# power-v29.net
KiCad netlist of a schematic drawn in Altium Designer
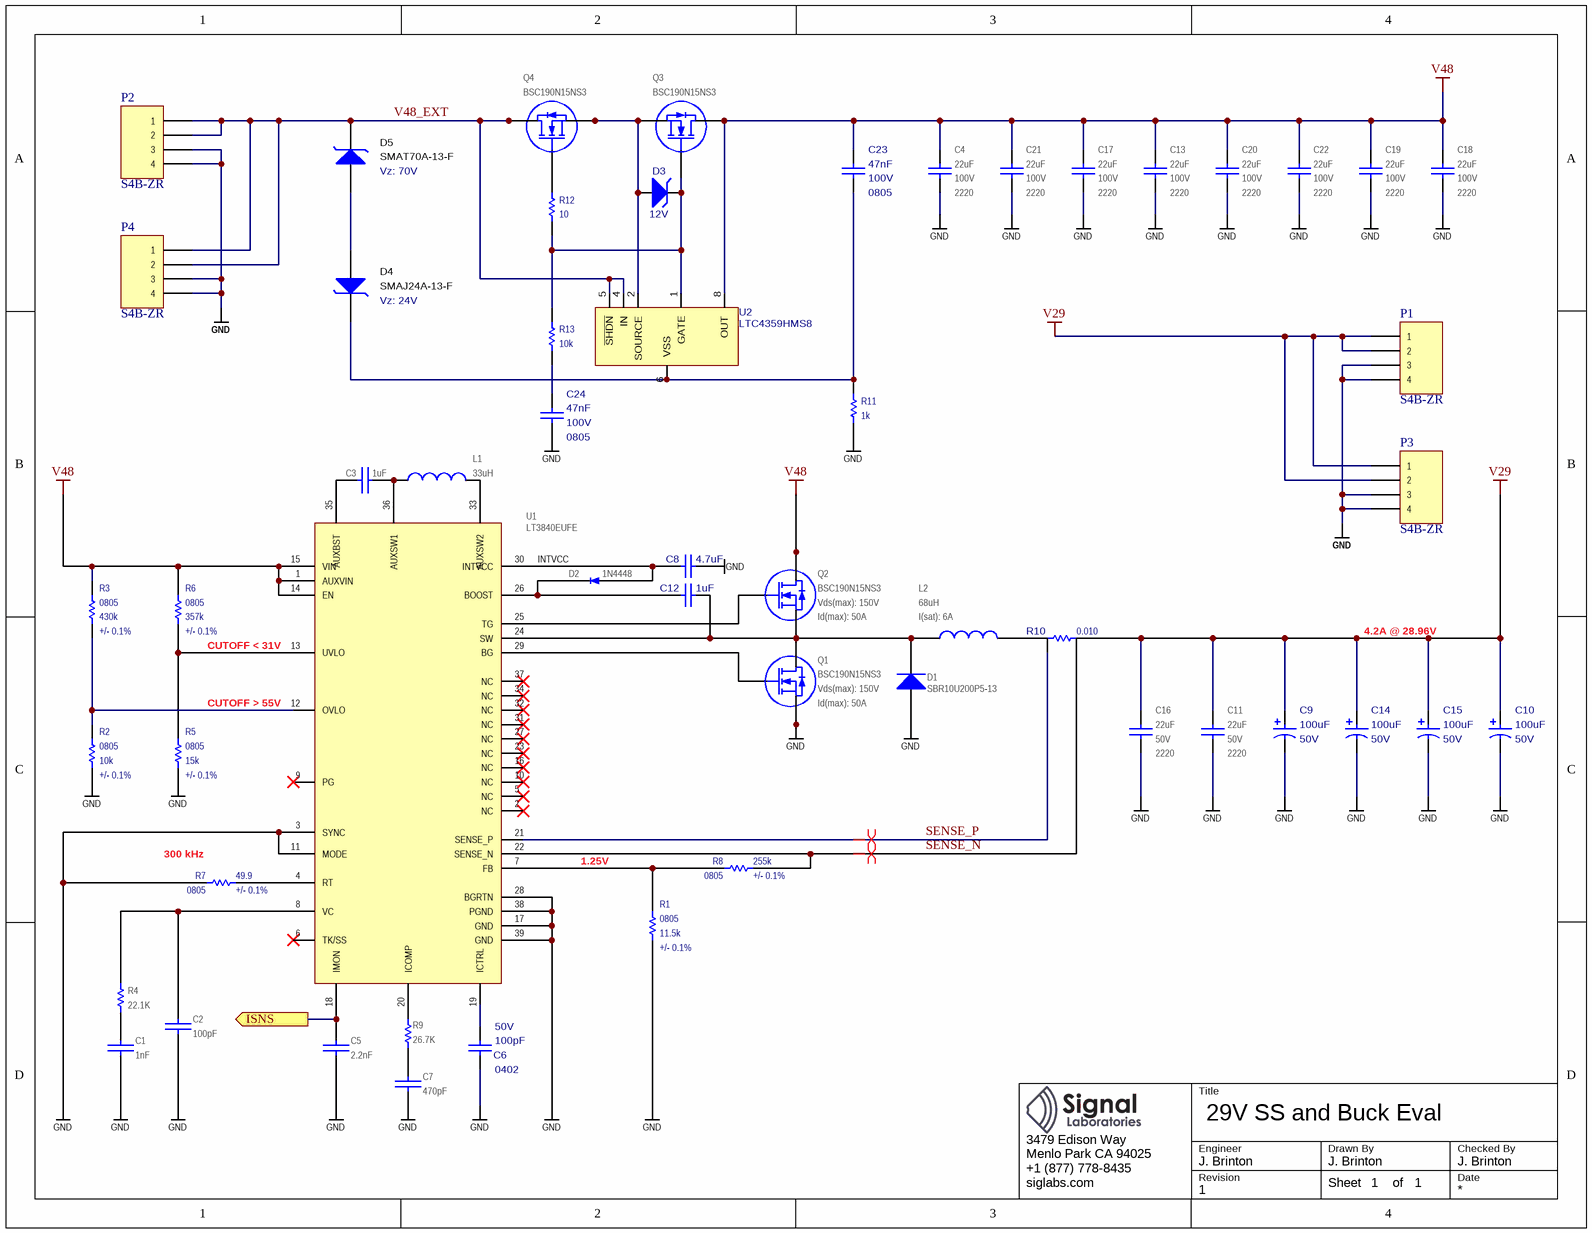
[diagram p0: power-v29.SchDoc]

(export (version "E")
  (design (tool "Eeschema 10.0.6"))
  (components
    (comp (ref "C1")
      (value "1nF")
      (footprint "CAPC100X50X55L25N")
      (description "Ceramic Capacitor 1nF ±5% 50V NP0 0402")
      (fields (field (name "MANUFACTURER") "Murata") (field (name "VOLTAGE") "50V"))
      (libsource (lib "*") (part "CAP"))
    )
    (comp (ref "C2")
      (value "100pF")
      (footprint "CAPC100X50X55L25N")
      (description "Ceramic Capacitor 100pF ±5% 50V NP0 0402")
      (fields (field (name "MANUFACTURER") "Murata") (field (name "VOLTAGE") "50V"))
      (libsource (lib "*") (part "CAP"))
    )
    (comp (ref "C3")
      (value "1uF")
      (footprint "CAPC100X50X55L25N")
      (description "Ceramic Capacitor 1uF ±10% 10V X5R 0402")
      (fields (field (name "MANUFACTURER") "Murata") (field (name "TOLERANCE") "±10%"))
      (libsource (lib "*") (part "CAP"))
    )
    (comp (ref "C4")
      (value "22uF")
      (footprint "CAPC600X500X500L160N")
      (description "Ceramic Capacitor 22uF ±20% 100V X7S Stacked")
      (fields
        (field (name "MANUFACTURER") "TDK")
        (field (name "TOLERANCE") "±20%")
        (field (name "VOLTAGE") "100V")
        (field (name "PACKAGE") "2220")
      )
      (libsource (lib "generic") (part "CAP"))
    )
    (comp (ref "C5")
      (value "2.2nF")
      (footprint "CAPC100X50X55L25N")
      (description "Ceramic Capacitor 2.2nF ±5% 25V NP0 0402")
      (fields (field (name "MANUFACTURER") "Kemet") (field (name "TOLERANCE") "±5%"))
      (libsource (lib "*") (part "CAP"))
    )
    (comp (ref "C6")
      (value "100pF")
      (footprint "CAPC160X80X90L20N")
      (description "Ceramic Capacitor 100pF ±10% 50V C0G 0402")
      (fields
        (field (name "MANUFACTURER") "Vishay")
        (field (name "TOLERANCE") "±10%")
        (field (name "PACKAGE") "0402")
        (field (name "VOLTAGE") "50V")
      )
      (libsource (lib "capacitors") (part "CAP"))
    )
    (comp (ref "C7")
      (value "470pF")
      (footprint "CAPC100X50X55L25N")
      (description "Ceramic Capacitor 470pF ±5% 50V X7R 0402")
      (fields (field (name "MANUFACTURER") "Murata") (field (name "VOLTAGE") "50V"))
      (libsource (lib "*") (part "CAP"))
    )
    (comp (ref "C8")
      (value "4.7uF")
      (footprint "CAPC160X80X90L20N")
      (description "Ceramic Capacitor 4.7uF ±10% 25V X7R 0805")
      (fields (field (name "MANUFACTURER") "Taiyo Yuden") (field (name "TOLERANCE") "±10%"))
      (libsource (lib "capacitors") (part "CAP"))
    )
    (comp (ref "C9")
      (value "100uF")
      (footprint "panasonic-ecg:CAPAE660X800D700L260X65N")
      (description "Aluminum Electrolytic Capacitor 100uF ±20% 50V")
      (fields
        (field (name "MANUFACTURER") "Panasonic")
        (field (name "TOLERANCE") "±20%")
        (field (name "VOLTAGE") "50V")
      )
      (libsource (lib "avx") (part "CAP_POL"))
    )
    (comp (ref "C10")
      (value "100uF")
      (footprint "panasonic-ecg:CAPAE660X800D700L260X65N")
      (description "Aluminum Electrolytic Capacitor 100uF ±20% 50V")
      (fields
        (field (name "MANUFACTURER") "Panasonic")
        (field (name "TOLERANCE") "±20%")
        (field (name "VOLTAGE") "50V")
      )
      (libsource (lib "avx") (part "CAP_POL"))
    )
    (comp (ref "C11")
      (value "22uF")
      (footprint "CAPC600X500X500L160N")
      (description "Ceramic Capacitor 22uF ±20% 50V X7S Stacked")
      (fields
        (field (name "MANUFACTURER") "TDK")
        (field (name "TOLERANCE") "±20%")
        (field (name "VOLTAGE") "50V")
        (field (name "PACKAGE") "2220")
      )
      (libsource (lib "generic") (part "CAP"))
    )
    (comp (ref "C12")
      (value "1uF")
      (footprint "CAPC160X80X90L20N")
      (description "Ceramic Capacitor 1uF ±10% 50V X7R 0805")
      (fields (field (name "MANUFACTURER") "Taiyo Yuden") (field (name "TOLERANCE") "±10%"))
      (libsource (lib "capacitors") (part "CAP"))
    )
    (comp (ref "C13")
      (value "22uF")
      (footprint "CAPC600X500X500L160N")
      (description "Ceramic Capacitor 22uF ±20% 100V X7S Stacked")
      (fields
        (field (name "MANUFACTURER") "TDK")
        (field (name "TOLERANCE") "±20%")
        (field (name "VOLTAGE") "100V")
        (field (name "PACKAGE") "2220")
      )
      (libsource (lib "generic") (part "CAP"))
    )
    (comp (ref "C14")
      (value "100uF")
      (footprint "panasonic-ecg:CAPAE660X800D700L260X65N")
      (description "Aluminum Electrolytic Capacitor 100uF ±20% 50V")
      (fields
        (field (name "MANUFACTURER") "Panasonic")
        (field (name "TOLERANCE") "±20%")
        (field (name "VOLTAGE") "50V")
      )
      (libsource (lib "avx") (part "CAP_POL"))
    )
    (comp (ref "C15")
      (value "100uF")
      (footprint "panasonic-ecg:CAPAE660X800D700L260X65N")
      (description "Aluminum Electrolytic Capacitor 100uF ±20% 50V")
      (fields
        (field (name "MANUFACTURER") "Panasonic")
        (field (name "TOLERANCE") "±20%")
        (field (name "VOLTAGE") "50V")
      )
      (libsource (lib "avx") (part "CAP_POL"))
    )
    (comp (ref "C16")
      (value "22uF")
      (footprint "CAPC600X500X500L160N")
      (description "Ceramic Capacitor 22uF ±20% 50V X7S Stacked")
      (fields
        (field (name "MANUFACTURER") "TDK")
        (field (name "TOLERANCE") "±20%")
        (field (name "VOLTAGE") "50V")
        (field (name "PACKAGE") "2220")
      )
      (libsource (lib "generic") (part "CAP"))
    )
    (comp (ref "C17")
      (value "22uF")
      (footprint "CAPC600X500X500L160N")
      (description "Ceramic Capacitor 22uF ±20% 100V X7S Stacked")
      (fields
        (field (name "MANUFACTURER") "TDK")
        (field (name "TOLERANCE") "±20%")
        (field (name "VOLTAGE") "100V")
        (field (name "PACKAGE") "2220")
      )
      (libsource (lib "generic") (part "CAP"))
    )
    (comp (ref "C18")
      (value "22uF")
      (footprint "CAPC600X500X500L160N")
      (description "Ceramic Capacitor 22uF ±20% 100V X7S Stacked")
      (fields
        (field (name "MANUFACTURER") "TDK")
        (field (name "TOLERANCE") "±20%")
        (field (name "VOLTAGE") "100V")
        (field (name "PACKAGE") "2220")
      )
      (libsource (lib "generic") (part "CAP"))
    )
    (comp (ref "C19")
      (value "22uF")
      (footprint "CAPC600X500X500L160N")
      (description "Ceramic Capacitor 22uF ±20% 100V X7S Stacked")
      (fields
        (field (name "MANUFACTURER") "TDK")
        (field (name "TOLERANCE") "±20%")
        (field (name "VOLTAGE") "100V")
        (field (name "PACKAGE") "2220")
      )
      (libsource (lib "generic") (part "CAP"))
    )
    (comp (ref "C20")
      (value "22uF")
      (footprint "CAPC600X500X500L160N")
      (description "Ceramic Capacitor 22uF ±20% 100V X7S Stacked")
      (fields
        (field (name "MANUFACTURER") "TDK")
        (field (name "TOLERANCE") "±20%")
        (field (name "VOLTAGE") "100V")
        (field (name "PACKAGE") "2220")
      )
      (libsource (lib "generic") (part "CAP"))
    )
    (comp (ref "C21")
      (value "22uF")
      (footprint "CAPC600X500X500L160N")
      (description "Ceramic Capacitor 22uF ±20% 100V X7S Stacked")
      (fields
        (field (name "MANUFACTURER") "TDK")
        (field (name "TOLERANCE") "±20%")
        (field (name "VOLTAGE") "100V")
        (field (name "PACKAGE") "2220")
      )
      (libsource (lib "generic") (part "CAP"))
    )
    (comp (ref "C22")
      (value "22uF")
      (footprint "CAPC600X500X500L160N")
      (description "Ceramic Capacitor 22uF ±20% 100V X7S Stacked")
      (fields
        (field (name "MANUFACTURER") "TDK")
        (field (name "TOLERANCE") "±20%")
        (field (name "VOLTAGE") "100V")
        (field (name "PACKAGE") "2220")
      )
      (libsource (lib "generic") (part "CAP"))
    )
    (comp (ref "C23")
      (value "47nF")
      (footprint "CAPC200X125X145L45N")
      (description "Ceramic Capacitor 47nF ±10% 100V X7R 0805")
      (fields
        (field (name "MANUFACTURER") "Vishay")
        (field (name "TOLERANCE") "±10%")
        (field (name "PACKAGE") "0805")
        (field (name "VOLTAGE") "100V")
      )
      (libsource (lib "capacitors") (part "CAP"))
    )
    (comp (ref "C24")
      (value "47nF")
      (footprint "CAPC200X125X145L45N")
      (description "Ceramic Capacitor 47nF ±10% 100V X7R 0805")
      (fields
        (field (name "MANUFACTURER") "Vishay")
        (field (name "TOLERANCE") "±10%")
        (field (name "PACKAGE") "0805")
        (field (name "VOLTAGE") "100V")
      )
      (libsource (lib "capacitors") (part "CAP"))
    )
    (comp (ref "D1")
      (value "SBR10U200P5-13")
      (footprint "DIODES_POWERDI5")
      (description "Schottky Diode 200V 10A SMD")
      (fields (field (name "MANUFACTURER") "Diodes Inc"))
      (libsource (lib "diodes_inc") (part "PDS5100H"))
    )
    (comp (ref "D2")
      (value "1N4448HWS-7-F")
      (footprint "diodes_inc:SOD323")
      (description "Schottky Diode 80V 250mA SOD323")
      (fields (field (name "MANUFACTURER") "Diodes, Inc.") (field (name "ALTERNATIVE P/N") "1N4448"))
      (libsource (lib "diodes_inc") (part "1N4448HWS-7-F"))
    )
    (comp (ref "D3")
      (value "DDZ12BQ-7")
      (footprint "SOD123")
      (description "Zener Diode 12V 370mW SOD-123")
      (fields (field (name "MANUFACTURER") "Diodes, Inc.") (field (name "VZ") "12V"))
      (libsource (lib "generic") (part "ZENER"))
    )
    (comp (ref "D4")
      (value "SMAJ24A-13-F")
      (footprint "SMA")
      (description "TVS Diode 24V/38.9V SMA")
      (fields (field (name "MANUFACTURER") "Diodes, Inc.") (field (name "VZ") "24V"))
      (libsource (lib "generic") (part "TVS"))
    )
    (comp (ref "D5")
      (value "SMAT70A-13-F")
      (footprint "SMA")
      (description "TVS Diode 70V/100V SMA")
      (fields (field (name "MANUFACTURER") "Diodes, Inc.") (field (name "VZ") "70V"))
      (libsource (lib "generic") (part "TVS"))
    )
    (comp (ref "L1")
      (value "33uH")
      (footprint "coilcraft:ME3220")
      (description "Wirewound Power Inductor 33uH ±10% 500mA SMD")
      (fields (field (name "MANUFACTURER") "Coilcraft") (field (name "TOLERANCE") "±10%"))
      (libsource (lib "CamBoard_Pico_70.19K") (part "COIL"))
    )
    (comp (ref "L2")
      (value "68uH")
      (footprint "cooper:HCM1A1707")
      (description "Fixed Inductor 68uH, 6A(sat), SMD")
      (fields
        (field (name "MANUFACTURER") "Eaton")
        (field (name "I(SAT)") "6A")
        (field (name "Comment") "HCM1A1707-680-R")
      )
      (libsource (lib "CamBoard_Pico_70.19K") (part "COIL"))
    )
    (comp (ref "P1")
      (value "S4B-ZR")
      (footprint "jst:S4B-ZR")
      (description "1.5mm pitch right angle 6-position")
      (fields (field (name "MANUFACTURER") "JST"))
      (libsource (lib "jst") (part "S4B-ZR"))
    )
    (comp (ref "P2")
      (value "S4B-ZR")
      (footprint "jst:S4B-ZR")
      (description "1.5mm pitch right angle 6-position")
      (fields (field (name "MANUFACTURER") "JST"))
      (libsource (lib "") (part "S4B-ZR_1"))
    )
    (comp (ref "P3")
      (value "S4B-ZR")
      (footprint "jst:S4B-ZR")
      (description "1.5mm pitch right angle 6-position")
      (fields (field (name "MANUFACTURER") "JST"))
      (libsource (lib "jst") (part "S4B-ZR"))
    )
    (comp (ref "P4")
      (value "S4B-ZR")
      (footprint "jst:S4B-ZR")
      (description "1.5mm pitch right angle 6-position")
      (fields (field (name "MANUFACTURER") "JST"))
      (libsource (lib "") (part "S4B-ZR_1"))
    )
    (comp (ref "Q1")
      (value "BSC190N15NS3")
      (footprint "TDSON-8")
      (description "MOSFET N-Channel Enhancement Mode")
      (fields
        (field (name "MANUFACTURER") "Infineon")
        (field (name "VDS(MAX)") "150V")
        (field (name "ID(MAX)") "50A")
      )
      (libsource (lib "infinion") (part "BSC190N15NS3"))
    )
    (comp (ref "Q2")
      (value "BSC190N15NS3")
      (footprint "TDSON-8")
      (description "MOSFET N-Channel Enhancement Mode")
      (fields
        (field (name "MANUFACTURER") "Infineon")
        (field (name "VDS(MAX)") "150V")
        (field (name "ID(MAX)") "50A")
      )
      (libsource (lib "infinion") (part "BSC190N15NS3"))
    )
    (comp (ref "Q3")
      (value "BSC190N15NS3")
      (footprint "TDSON-8")
      (description "MOSFET N-Channel Enhancement Mode")
      (fields (field (name "MANUFACTURER") "Infineon"))
      (libsource (lib "infinion") (part "BSC190N15NS3"))
    )
    (comp (ref "Q4")
      (value "BSC190N15NS3")
      (footprint "TDSON-8")
      (description "MOSFET N-Channel Enhancement Mode")
      (fields (field (name "MANUFACTURER") "Infineon"))
      (libsource (lib "infinion") (part "BSC190N15NS3"))
    )
    (comp (ref "R1")
      (value "11.5k")
      (footprint "RESC2012X70N")
      (description "Thin Film Resistor 11.5k +/-0.1% SMD 0805")
      (fields
        (field (name "TOLERANCE") "+/- 0.1%")
        (field (name "MANUFACTURER") "Yageo")
        (field (name "PACKAGE") "0805")
        (field (name "Comment") "RT0805BRD0711K5L")
      )
      (libsource (lib "generic") (part "RES"))
    )
    (comp (ref "R2")
      (value "10k")
      (footprint "RESC2012X70N")
      (description "Thin Film Resistor 10k +/-0.1% SMD 0805")
      (fields
        (field (name "TOLERANCE") "+/- 0.1%")
        (field (name "MANUFACTURER") "Susumu")
        (field (name "PACKAGE") "0805")
        (field (name "Comment") "RG2012P-103-B-T5")
      )
      (libsource (lib "generic") (part "RES"))
    )
    (comp (ref "R3")
      (value "430k")
      (footprint "RESC2012X70N")
      (description "Thin Film Resistor 430k +/-0.1% SMD 0805")
      (fields
        (field (name "TOLERANCE") "+/- 0.1%")
        (field (name "MANUFACTURER") "Yageo")
        (field (name "PACKAGE") "0805")
        (field (name "Comment") "RT0805BRD07430KL")
      )
      (libsource (lib "generic") (part "RES"))
    )
    (comp (ref "R4")
      (value "22.1K")
      (footprint "generic:RESC1005X40N")
      (description "Thick Film Resistor 22.1k ±1% 0402")
      (fields (field (name "MANUFACTURER") "Panasonic") (field (name "TOLERANCE") "±1%"))
      (libsource (lib "Graviton") (part "RES 0402"))
    )
    (comp (ref "R5")
      (value "15k")
      (footprint "RESC2012X70N")
      (description "Thin Film Resistor 15k +/-0.1% SMD 0805")
      (fields
        (field (name "TOLERANCE") "+/- 0.1%")
        (field (name "MANUFACTURER") "Susumu")
        (field (name "PACKAGE") "0805")
        (field (name "Comment") "RG2012P-153-B-T5")
      )
      (libsource (lib "generic") (part "RES"))
    )
    (comp (ref "R6")
      (value "357k")
      (footprint "RESC2012X70N")
      (description "Thin Film Resistor 357k +/-0.1% SMD 0805")
      (fields
        (field (name "TOLERANCE") "+/- 0.1%")
        (field (name "MANUFACTURER") "Yageo")
        (field (name "PACKAGE") "0805")
        (field (name "Comment") "RT0805BRD07357KL")
      )
      (libsource (lib "generic") (part "RES"))
    )
    (comp (ref "R7")
      (value "49.9")
      (footprint "RESC2012X70N")
      (description "Thin Film Resistor 49 +/-0.1% SMD 0805")
      (fields
        (field (name "TOLERANCE") "+/- 0.1%")
        (field (name "MANUFACTURER") "Yageo")
        (field (name "PACKAGE") "0805")
        (field (name "Comment") "RT0805BRD0749R9L")
      )
      (libsource (lib "generic") (part "RES"))
    )
    (comp (ref "R8")
      (value "255k")
      (footprint "RESC2012X70N")
      (description "Thin Film Resistor 255k +/-0.1% SMD 0805")
      (fields
        (field (name "TOLERANCE") "+/- 0.1%")
        (field (name "MANUFACTURER") "Vishay")
        (field (name "PACKAGE") "0805")
        (field (name "Comment") "PTN0805E2553BST1")
      )
      (libsource (lib "generic") (part "RES"))
    )
    (comp (ref "R9")
      (value "26.7K")
      (footprint "generic:RESC1005X40N")
      (description "Thick Film Resistor 26.7k ±1% 0402")
      (fields (field (name "MANUFACTURER") "Panasonic") (field (name "TOLERANCE") "±1%"))
      (libsource (lib "Graviton") (part "RES 0402"))
    )
    (comp (ref "R10")
      (value "0.010")
      (footprint "ohmite:LVK20")
      (description "Current Sense Resistor 10 mOhms +/-0.5% SMD 4-Terminal")
      (fields (field (name "TOLERANCE") "+/-0.5%") (field (name "MANUFACTURER") "Ohmite"))
      (libsource (lib "bourns") (part "CST0612-FC-R002E"))
    )
    (comp (ref "R11")
      (value "1k")
      (footprint "RESC2012X70N")
      (description "Thin Film Resistor 1k +/-1% SMD 0805")
      (fields (field (name "TOLERANCE") "+/- 1%") (field (name "MANUFACTURER") "Yageo"))
      (libsource (lib "generic") (part "RES"))
    )
    (comp (ref "R12")
      (value "10")
      (footprint "RESC2012X70N")
      (description "Thin Film Resistor 10 +/-1% SMD 0805")
      (fields (field (name "TOLERANCE") "+/- 1%") (field (name "MANUFACTURER") "Yageo"))
      (libsource (lib "generic") (part "RES"))
    )
    (comp (ref "R13")
      (value "10k")
      (footprint "RESC2012X70N")
      (description "Thin Film Resistor 10k +/-1% SMD 0805")
      (fields (field (name "TOLERANCE") "+/- 1%") (field (name "MANUFACTURER") "Yageo"))
      (libsource (lib "generic") (part "RES"))
    )
    (comp (ref "U1")
      (value "LT3840EUFE")
      (footprint "linear:QFN39P40_600X400X80L40X20T465X265N")
      (description "Synchronous Regulator Controller")
      (fields (field (name "MANUFACTURER") "Linear Technologies"))
      (libsource (lib "linear") (part "LT3840EUFE"))
    )
    (comp (ref "U2")
      (value "LTC4359HMS8")
      (footprint "generic:MSOP8")
      (description "Ideal Diode Controller")
      (fields (field (name "MANUFACTURER") "Linear Technology"))
      (libsource (lib "linear") (part "LTC4359HMS8"))
    )
  )
  (nets
    (net (code "1") (name "/INTVCC") (class "Default")
      (node (ref "C8") (pin "1") (pinfunction "1_1") (pintype "passive"))
      (node (ref "D2") (pin "A") (pinfunction "A_A") (pintype "passive"))
      (node (ref "U1") (pin "30") (pinfunction "INTVCC_30") (pintype "passive"))
    )
    (net (code "2") (name "/ISNS") (class "Default")
      (node (ref "C5") (pin "1") (pinfunction "1_1") (pintype "passive"))
      (node (ref "U1") (pin "18") (pinfunction "IMON_18") (pintype "passive"))
    )
    (net (code "3") (name "/SENSE_N") (class "Default")
      (node (ref "R10") (pin "2") (pinfunction "2_2") (pintype "passive"))
      (node (ref "R8") (pin "1") (pinfunction "1_1") (pintype "passive"))
      (node (ref "U1") (pin "22") (pinfunction "SENSE_N_22") (pintype "passive"))
    )
    (net (code "4") (name "/SENSE_P") (class "Default")
      (node (ref "R10") (pin "3") (pinfunction "3_3") (pintype "passive"))
      (node (ref "U1") (pin "21") (pinfunction "SENSE_P_21") (pintype "passive"))
    )
    (net (code "5") (name "/V48_EXT") (class "Default")
      (node (ref "D5") (pin "2") (pinfunction "K_2") (pintype "passive"))
      (node (ref "P2") (pin "1") (pinfunction "1_1") (pintype "passive"))
      (node (ref "P2") (pin "2") (pinfunction "2_2") (pintype "passive"))
      (node (ref "P4") (pin "1") (pinfunction "1_1") (pintype "passive"))
      (node (ref "P4") (pin "2") (pinfunction "2_2") (pintype "passive"))
      (node (ref "Q4") (pin "5") (pinfunction "D_5") (pintype "passive"))
      (node (ref "Q4") (pin "6") (pinfunction "D_6") (pintype "passive"))
      (node (ref "Q4") (pin "7") (pinfunction "D_7") (pintype "passive"))
      (node (ref "Q4") (pin "8") (pinfunction "D_8") (pintype "passive"))
      (node (ref "Q4") (pin "9") (pinfunction "D_9") (pintype "passive"))
      (node (ref "U2") (pin "4") (pinfunction "IN_4") (pintype "passive"))
      (node (ref "U2") (pin "5") (pinfunction "SHDN_5") (pintype "passive"))
    )
    (net (code "6") (name "GND") (class "Default")
      (node (ref "C1") (pin "2") (pinfunction "2_2") (pintype "passive"))
      (node (ref "C10") (pin "2") (pinfunction "2_2") (pintype "passive"))
      (node (ref "C11") (pin "1") (pinfunction "1_1") (pintype "passive"))
      (node (ref "C13") (pin "1") (pinfunction "1_1") (pintype "passive"))
      (node (ref "C14") (pin "2") (pinfunction "2_2") (pintype "passive"))
      (node (ref "C15") (pin "2") (pinfunction "2_2") (pintype "passive"))
      (node (ref "C16") (pin "1") (pinfunction "1_1") (pintype "passive"))
      (node (ref "C17") (pin "1") (pinfunction "1_1") (pintype "passive"))
      (node (ref "C18") (pin "1") (pinfunction "1_1") (pintype "passive"))
      (node (ref "C19") (pin "1") (pinfunction "1_1") (pintype "passive"))
      (node (ref "C2") (pin "1") (pinfunction "1_1") (pintype "passive"))
      (node (ref "C20") (pin "1") (pinfunction "1_1") (pintype "passive"))
      (node (ref "C21") (pin "1") (pinfunction "1_1") (pintype "passive"))
      (node (ref "C22") (pin "1") (pinfunction "1_1") (pintype "passive"))
      (node (ref "C24") (pin "2") (pinfunction "2_2") (pintype "passive"))
      (node (ref "C4") (pin "1") (pinfunction "1_1") (pintype "passive"))
      (node (ref "C5") (pin "2") (pinfunction "2_2") (pintype "passive"))
      (node (ref "C6") (pin "2") (pinfunction "2_2") (pintype "passive"))
      (node (ref "C7") (pin "1") (pinfunction "1_1") (pintype "passive"))
      (node (ref "C8") (pin "2") (pinfunction "2_2") (pintype "passive"))
      (node (ref "C9") (pin "2") (pinfunction "2_2") (pintype "passive"))
      (node (ref "D1") (pin "A") (pinfunction "A_A") (pintype "power_in"))
      (node (ref "P1") (pin "3") (pinfunction "3_3") (pintype "passive"))
      (node (ref "P1") (pin "4") (pinfunction "4_4") (pintype "passive"))
      (node (ref "P2") (pin "3") (pinfunction "3_3") (pintype "passive"))
      (node (ref "P2") (pin "4") (pinfunction "4_4") (pintype "passive"))
      (node (ref "P3") (pin "3") (pinfunction "3_3") (pintype "passive"))
      (node (ref "P3") (pin "4") (pinfunction "4_4") (pintype "passive"))
      (node (ref "P4") (pin "3") (pinfunction "3_3") (pintype "passive"))
      (node (ref "P4") (pin "4") (pinfunction "4_4") (pintype "passive"))
      (node (ref "Q1") (pin "1") (pinfunction "S_1") (pintype "passive"))
      (node (ref "Q1") (pin "2") (pinfunction "S_2") (pintype "passive"))
      (node (ref "Q1") (pin "3") (pinfunction "S_3") (pintype "passive"))
      (node (ref "R1") (pin "1") (pinfunction "1_1") (pintype "passive"))
      (node (ref "R11") (pin "1") (pinfunction "1_1") (pintype "passive"))
      (node (ref "R2") (pin "1") (pinfunction "1_1") (pintype "passive"))
      (node (ref "R5") (pin "1") (pinfunction "1_1") (pintype "passive"))
      (node (ref "R7") (pin "2") (pinfunction "2_2") (pintype "passive"))
      (node (ref "U1") (pin "11") (pinfunction "MODE_11") (pintype "passive"))
      (node (ref "U1") (pin "17") (pinfunction "GND_17") (pintype "passive"))
      (node (ref "U1") (pin "28") (pinfunction "BGRTN_28") (pintype "passive"))
      (node (ref "U1") (pin "3") (pinfunction "SYNC_3") (pintype "passive"))
      (node (ref "U1") (pin "38") (pinfunction "PGND_38") (pintype "passive"))
      (node (ref "U1") (pin "39") (pinfunction "GND_39") (pintype "passive"))
    )
    (net (code "7") (name "Net-(C1-Pad1)") (class "Default")
      (node (ref "C1") (pin "1") (pinfunction "1_1") (pintype "passive"))
      (node (ref "R4") (pin "1") (pinfunction "1_1") (pintype "passive"))
    )
    (net (code "8") (name "Net-(C7-Pad2)") (class "Default")
      (node (ref "C7") (pin "2") (pinfunction "2_2") (pintype "passive"))
      (node (ref "R9") (pin "2") (pinfunction "2_2") (pintype "passive"))
    )
    (net (code "9") (name "Net-(C24-Pad1)") (class "Default")
      (node (ref "C24") (pin "1") (pinfunction "1_1") (pintype "passive"))
      (node (ref "R13") (pin "1") (pinfunction "1_1") (pintype "passive"))
    )
    (net (code "10") (name "Net-(D3-A)") (class "Default")
      (node (ref "D3") (pin "1") (pinfunction "A_1") (pintype "power_in"))
      (node (ref "Q3") (pin "1") (pinfunction "S_1") (pintype "passive"))
      (node (ref "Q3") (pin "2") (pinfunction "S_2") (pintype "passive"))
      (node (ref "Q3") (pin "3") (pinfunction "S_3") (pintype "passive"))
      (node (ref "Q4") (pin "1") (pinfunction "S_1") (pintype "passive"))
      (node (ref "Q4") (pin "2") (pinfunction "S_2") (pintype "passive"))
      (node (ref "Q4") (pin "3") (pinfunction "S_3") (pintype "passive"))
      (node (ref "U2") (pin "2") (pinfunction "SOURCE_2") (pintype "passive"))
    )
    (net (code "11") (name "Net-(D3-K)") (class "Default")
      (node (ref "D3") (pin "2") (pinfunction "K_2") (pintype "passive"))
      (node (ref "Q3") (pin "4") (pinfunction "G_4") (pintype "passive"))
      (node (ref "R12") (pin "1") (pinfunction "1_1") (pintype "passive"))
      (node (ref "R13") (pin "2") (pinfunction "2_2") (pintype "passive"))
      (node (ref "U2") (pin "1") (pinfunction "GATE_1") (pintype "passive"))
    )
    (net (code "12") (name "Net-(D4-A)") (class "Default")
      (node (ref "D4") (pin "1") (pinfunction "A_1") (pintype "power_in"))
      (node (ref "D5") (pin "1") (pinfunction "A_1") (pintype "power_in"))
    )
    (net (code "13") (name "Net-(D4-K)") (class "Default")
      (node (ref "C23") (pin "2") (pinfunction "2_2") (pintype "passive"))
      (node (ref "D4") (pin "2") (pinfunction "K_2") (pintype "passive"))
      (node (ref "R11") (pin "2") (pinfunction "2_2") (pintype "passive"))
      (node (ref "U2") (pin "6") (pinfunction "VSS_6") (pintype "passive"))
    )
    (net (code "14") (name "Net-(L2-Pad2)") (class "Default")
      (node (ref "L2") (pin "2") (pinfunction "2_2") (pintype "passive"))
      (node (ref "R10") (pin "4") (pinfunction "4_4") (pintype "passive"))
    )
    (net (code "15") (name "Net-(Q1-G)") (class "Default")
      (node (ref "Q1") (pin "4") (pinfunction "G_4") (pintype "passive"))
      (node (ref "U1") (pin "29") (pinfunction "BG_29") (pintype "passive"))
    )
    (net (code "16") (name "Net-(Q2-G)") (class "Default")
      (node (ref "Q2") (pin "4") (pinfunction "G_4") (pintype "passive"))
      (node (ref "U1") (pin "25") (pinfunction "TG_25") (pintype "passive"))
    )
    (net (code "17") (name "Net-(Q4-G)") (class "Default")
      (node (ref "Q4") (pin "4") (pinfunction "G_4") (pintype "passive"))
      (node (ref "R12") (pin "2") (pinfunction "2_2") (pintype "passive"))
    )
    (net (code "18") (name "Net-(U1-AUXBST)") (class "Default")
      (node (ref "C3") (pin "2") (pinfunction "2_2") (pintype "passive"))
      (node (ref "U1") (pin "35") (pinfunction "AUXBST_35") (pintype "passive"))
    )
    (net (code "19") (name "Net-(U1-AUXSW1)") (class "Default")
      (node (ref "C3") (pin "1") (pinfunction "1_1") (pintype "passive"))
      (node (ref "L1") (pin "1") (pinfunction "1_1") (pintype "passive"))
      (node (ref "U1") (pin "36") (pinfunction "AUXSW1_36") (pintype "passive"))
    )
    (net (code "20") (name "Net-(U1-AUXSW2)") (class "Default")
      (node (ref "L1") (pin "2") (pinfunction "2_2") (pintype "passive"))
      (node (ref "U1") (pin "33") (pinfunction "AUXSW2_33") (pintype "passive"))
    )
    (net (code "21") (name "Net-(U1-BOOST)") (class "Default")
      (node (ref "C12") (pin "1") (pinfunction "1_1") (pintype "passive"))
      (node (ref "D2") (pin "K") (pinfunction "K_K") (pintype "passive"))
      (node (ref "U1") (pin "26") (pinfunction "BOOST_26") (pintype "passive"))
    )
    (net (code "22") (name "Net-(U1-FB)") (class "Default")
      (node (ref "R1") (pin "2") (pinfunction "2_2") (pintype "passive"))
      (node (ref "R8") (pin "2") (pinfunction "2_2") (pintype "passive"))
      (node (ref "U1") (pin "7") (pinfunction "FB_7") (pintype "passive"))
    )
    (net (code "23") (name "Net-(U1-ICOMP)") (class "Default")
      (node (ref "R9") (pin "1") (pinfunction "1_1") (pintype "passive"))
      (node (ref "U1") (pin "20") (pinfunction "ICOMP_20") (pintype "passive"))
    )
    (net (code "24") (name "Net-(U1-ICTRL)") (class "Default")
      (node (ref "C6") (pin "1") (pinfunction "1_1") (pintype "passive"))
      (node (ref "U1") (pin "19") (pinfunction "ICTRL_19") (pintype "passive"))
    )
    (net (code "25") (name "Net-(U1-OVLO)") (class "Default")
      (node (ref "R2") (pin "2") (pinfunction "2_2") (pintype "passive"))
      (node (ref "R3") (pin "1") (pinfunction "1_1") (pintype "passive"))
      (node (ref "U1") (pin "12") (pinfunction "OVLO_12") (pintype "passive"))
    )
    (net (code "26") (name "Net-(U1-RT)") (class "Default")
      (node (ref "R7") (pin "1") (pinfunction "1_1") (pintype "passive"))
      (node (ref "U1") (pin "4") (pinfunction "RT_4") (pintype "passive"))
    )
    (net (code "27") (name "Net-(U1-SW)") (class "Default")
      (node (ref "C12") (pin "2") (pinfunction "2_2") (pintype "passive"))
      (node (ref "D1") (pin "K") (pinfunction "K_K") (pintype "passive"))
      (node (ref "L2") (pin "1") (pinfunction "1_1") (pintype "passive"))
      (node (ref "Q1") (pin "5") (pinfunction "D_5") (pintype "passive"))
      (node (ref "Q1") (pin "6") (pinfunction "D_6") (pintype "passive"))
      (node (ref "Q1") (pin "7") (pinfunction "D_7") (pintype "passive"))
      (node (ref "Q1") (pin "8") (pinfunction "D_8") (pintype "passive"))
      (node (ref "Q1") (pin "9") (pinfunction "D_9") (pintype "passive"))
      (node (ref "Q2") (pin "1") (pinfunction "S_1") (pintype "passive"))
      (node (ref "Q2") (pin "2") (pinfunction "S_2") (pintype "passive"))
      (node (ref "Q2") (pin "3") (pinfunction "S_3") (pintype "passive"))
      (node (ref "U1") (pin "24") (pinfunction "SW_24") (pintype "passive"))
    )
    (net (code "28") (name "Net-(U1-UVLO)") (class "Default")
      (node (ref "R5") (pin "2") (pinfunction "2_2") (pintype "passive"))
      (node (ref "R6") (pin "1") (pinfunction "1_1") (pintype "passive"))
      (node (ref "U1") (pin "13") (pinfunction "UVLO_13") (pintype "passive"))
    )
    (net (code "29") (name "Net-(U1-VC)") (class "Default")
      (node (ref "C2") (pin "2") (pinfunction "2_2") (pintype "passive"))
      (node (ref "R4") (pin "2") (pinfunction "2_2") (pintype "passive"))
      (node (ref "U1") (pin "8") (pinfunction "VC_8") (pintype "passive"))
    )
    (net (code "30") (name "V29") (class "Default")
      (node (ref "C10") (pin "1") (pinfunction "1_1") (pintype "passive"))
      (node (ref "C11") (pin "2") (pinfunction "2_2") (pintype "passive"))
      (node (ref "C14") (pin "1") (pinfunction "1_1") (pintype "passive"))
      (node (ref "C15") (pin "1") (pinfunction "1_1") (pintype "passive"))
      (node (ref "C16") (pin "2") (pinfunction "2_2") (pintype "passive"))
      (node (ref "C9") (pin "1") (pinfunction "1_1") (pintype "passive"))
      (node (ref "P1") (pin "1") (pinfunction "1_1") (pintype "passive"))
      (node (ref "P1") (pin "2") (pinfunction "2_2") (pintype "passive"))
      (node (ref "P3") (pin "1") (pinfunction "1_1") (pintype "passive"))
      (node (ref "P3") (pin "2") (pinfunction "2_2") (pintype "passive"))
      (node (ref "R10") (pin "1") (pinfunction "1_1") (pintype "passive"))
    )
    (net (code "31") (name "V48") (class "Default")
      (node (ref "C13") (pin "2") (pinfunction "2_2") (pintype "passive"))
      (node (ref "C17") (pin "2") (pinfunction "2_2") (pintype "passive"))
      (node (ref "C18") (pin "2") (pinfunction "2_2") (pintype "passive"))
      (node (ref "C19") (pin "2") (pinfunction "2_2") (pintype "passive"))
      (node (ref "C20") (pin "2") (pinfunction "2_2") (pintype "passive"))
      (node (ref "C21") (pin "2") (pinfunction "2_2") (pintype "passive"))
      (node (ref "C22") (pin "2") (pinfunction "2_2") (pintype "passive"))
      (node (ref "C23") (pin "1") (pinfunction "1_1") (pintype "passive"))
      (node (ref "C4") (pin "2") (pinfunction "2_2") (pintype "passive"))
      (node (ref "Q2") (pin "5") (pinfunction "D_5") (pintype "passive"))
      (node (ref "Q2") (pin "6") (pinfunction "D_6") (pintype "passive"))
      (node (ref "Q2") (pin "7") (pinfunction "D_7") (pintype "passive"))
      (node (ref "Q2") (pin "8") (pinfunction "D_8") (pintype "passive"))
      (node (ref "Q2") (pin "9") (pinfunction "D_9") (pintype "passive"))
      (node (ref "Q3") (pin "5") (pinfunction "D_5") (pintype "passive"))
      (node (ref "Q3") (pin "6") (pinfunction "D_6") (pintype "passive"))
      (node (ref "Q3") (pin "7") (pinfunction "D_7") (pintype "passive"))
      (node (ref "Q3") (pin "8") (pinfunction "D_8") (pintype "passive"))
      (node (ref "Q3") (pin "9") (pinfunction "D_9") (pintype "passive"))
      (node (ref "R3") (pin "2") (pinfunction "2_2") (pintype "passive"))
      (node (ref "R6") (pin "2") (pinfunction "2_2") (pintype "passive"))
      (node (ref "U1") (pin "1") (pinfunction "AUXVIN_1") (pintype "passive"))
      (node (ref "U1") (pin "14") (pinfunction "EN_14") (pintype "passive"))
      (node (ref "U1") (pin "15") (pinfunction "VIN_15") (pintype "passive"))
      (node (ref "U2") (pin "8") (pinfunction "OUT_8") (pintype "passive"))
    )
    (net (code "32") (name "unconnected-(U1-NC-Pad2)") (class "Default")
      (node (ref "U1") (pin "2") (pinfunction "NC_2") (pintype "passive+no_connect"))
    )
    (net (code "33") (name "unconnected-(U1-NC-Pad5)") (class "Default")
      (node (ref "U1") (pin "5") (pinfunction "NC_5") (pintype "passive+no_connect"))
    )
    (net (code "34") (name "unconnected-(U1-NC-Pad10)") (class "Default")
      (node (ref "U1") (pin "10") (pinfunction "NC_10") (pintype "passive+no_connect"))
    )
    (net (code "35") (name "unconnected-(U1-NC-Pad16)") (class "Default")
      (node (ref "U1") (pin "16") (pinfunction "NC_16") (pintype "passive+no_connect"))
    )
    (net (code "36") (name "unconnected-(U1-NC-Pad23)") (class "Default")
      (node (ref "U1") (pin "23") (pinfunction "NC_23") (pintype "passive+no_connect"))
    )
    (net (code "37") (name "unconnected-(U1-NC-Pad27)") (class "Default")
      (node (ref "U1") (pin "27") (pinfunction "NC_27") (pintype "passive+no_connect"))
    )
    (net (code "38") (name "unconnected-(U1-NC-Pad31)") (class "Default")
      (node (ref "U1") (pin "31") (pinfunction "NC_31") (pintype "passive+no_connect"))
    )
    (net (code "39") (name "unconnected-(U1-NC-Pad32)") (class "Default")
      (node (ref "U1") (pin "32") (pinfunction "NC_32") (pintype "passive+no_connect"))
    )
    (net (code "40") (name "unconnected-(U1-NC-Pad34)") (class "Default")
      (node (ref "U1") (pin "34") (pinfunction "NC_34") (pintype "passive+no_connect"))
    )
    (net (code "41") (name "unconnected-(U1-NC-Pad37)") (class "Default")
      (node (ref "U1") (pin "37") (pinfunction "NC_37") (pintype "passive+no_connect"))
    )
    (net (code "42") (name "unconnected-(U1-PG-Pad9)") (class "Default")
      (node (ref "U1") (pin "9") (pinfunction "PG_9") (pintype "passive+no_connect"))
    )
    (net (code "43") (name "unconnected-(U1-TK{slash}SS-Pad6)") (class "Default")
      (node (ref "U1") (pin "6") (pinfunction "TK/SS_6") (pintype "passive+no_connect"))
    )
    (net (code "44") (name "unconnected-(U2-NC-Pad3)") (class "Default")
      (node (ref "U2") (pin "3") (pinfunction "NC_3") (pintype "passive"))
    )
    (net (code "45") (name "unconnected-(U2-NC-Pad7)") (class "Default")
      (node (ref "U2") (pin "7") (pinfunction "NC_7") (pintype "passive"))
    )
  )
)
